# PowerUpDelay-SCR.net
KiCad netlist of a schematic drawn in Altium Designer
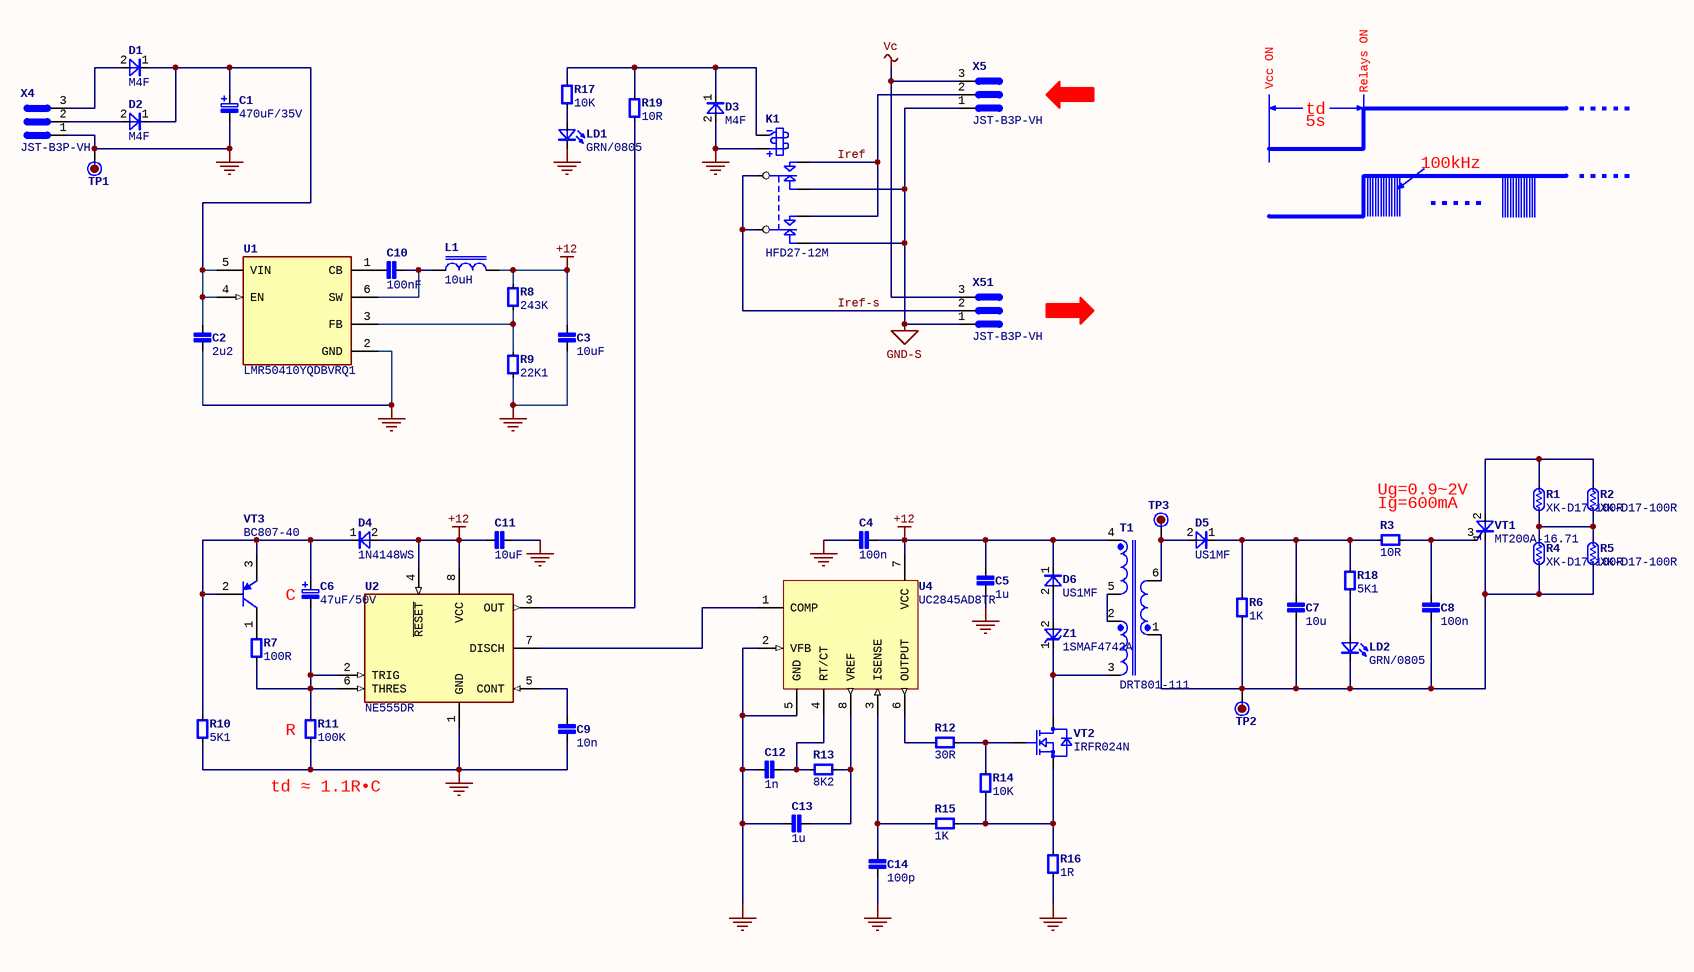
[diagram p0: PowerUpDelay-SCR.SchDoc]

(export (version "E")
  (design (tool "Eeschema 10.0.6"))
  (components
    (comp (ref "C1")
      (value "470uF/35V")
      (footprint "RB5M/D10")
      (libsource (lib "User_leo") (part "CAPACITOR POL(S)"))
    )
    (comp (ref "C2") (value "2u2") (footprint "CAPC1206N") (libsource (lib "*") (part "CAPACITOR(S)")))
    (comp (ref "C3") (value "10uF") (footprint "CAPC0805N") (libsource (lib "*") (part "CAPACITOR(S)")))
    (comp (ref "C4") (value "100n") (footprint "CAPC0805N") (libsource (lib "主控板") (part "CAPACITOR(S)")))
    (comp (ref "C5") (value "1u") (footprint "CAPC0805N") (libsource (lib "主控板") (part "CAPACITOR(S)")))
    (comp (ref "C6")
      (value "47uF/50V")
      (footprint "RB2.5M/D6.3")
      (libsource (lib "User_leo") (part "CAPACITOR POL(S)"))
    )
    (comp (ref "C7") (value "10u") (footprint "CAPC1206N") (libsource (lib "主控板") (part "CAPACITOR(S)")))
    (comp (ref "C8") (value "100n") (footprint "CAPC1206N") (libsource (lib "主控板") (part "CAPACITOR(S)")))
    (comp (ref "C9") (value "10n") (footprint "CAPC0805N") (libsource (lib "主控板") (part "CAPACITOR(S)")))
    (comp (ref "C10") (value "100nF") (footprint "CAPC0805N") (libsource (lib "*") (part "CAPACITOR(S)")))
    (comp (ref "C11") (value "10uF") (footprint "CAPC0805N") (libsource (lib "*") (part "CAPACITOR(S)")))
    (comp (ref "C12") (value "1n") (footprint "CAPC0805N") (libsource (lib "主控板") (part "CAPACITOR(S)")))
    (comp (ref "C13") (value "1u") (footprint "CAPC0805N") (libsource (lib "主控板") (part "CAPACITOR(S)")))
    (comp (ref "C14") (value "100p") (footprint "CAPC0805N") (libsource (lib "主控板") (part "CAPACITOR(S)")))
    (comp (ref "D1")
      (value "M4F")
      (footprint "SMAF")
      (description "二极管")
      (libsource (lib "User_leo") (part "DIODE(S)"))
    )
    (comp (ref "D2")
      (value "M4F")
      (footprint "SMAF")
      (description "二极管")
      (libsource (lib "User_leo") (part "DIODE(S)"))
    )
    (comp (ref "D3")
      (value "M4F")
      (footprint "SMAF")
      (description "二极管")
      (libsource (lib "User_leo") (part "DIODE(S)"))
    )
    (comp (ref "D4")
      (value "1N4148WS")
      (footprint "SOD-323F-1K2A")
      (description "二极管")
      (libsource (lib "User_leo") (part "DIODE(S)"))
    )
    (comp (ref "D5")
      (value "US1MF")
      (footprint "SMAF")
      (description "二极管")
      (libsource (lib "User_leo") (part "DIODE(S)"))
    )
    (comp (ref "D6")
      (value "US1MF")
      (footprint "SMAF")
      (description "二极管")
      (libsource (lib "User_leo") (part "DIODE(S)"))
    )
    (comp (ref "K1")
      (value "HFD27-12M")
      (footprint "RLY-DPDT")
      (description "继电器")
      (libsource (lib "d_user1") (part "RELAY-DPDT"))
    )
    (comp (ref "L1") (value "10uH") (footprint "INDP4040X20N") (libsource (lib "User_leo") (part "IND")))
    (comp (ref "LD1")
      (value "GRN/0805")
      (footprint "LEDC0805N")
      (libsource (lib "ARM-Stub 主控板") (part "LED(S)"))
    )
    (comp (ref "LD2")
      (value "GRN/0805")
      (footprint "LEDC0805N")
      (libsource (lib "ARM-Stub 主控板") (part "LED(S)"))
    )
    (comp (ref "R1")
      (value "XK-D17-100R")
      (footprint "PTC-X17")
      (description "None Liner Resistor")
      (libsource (lib "User_leo") (part "RESISTOR(S) NL"))
    )
    (comp (ref "R2")
      (value "XK-D17-100R")
      (footprint "PTC-X17")
      (description "None Liner Resistor")
      (libsource (lib "User_leo") (part "RESISTOR(S) NL"))
    )
    (comp (ref "R3") (value "10R") (footprint "RESC1206N") (libsource (lib "*") (part "RESISTOR(S)")))
    (comp (ref "R4")
      (value "XK-D17-100R")
      (footprint "PTC-X17")
      (description "None Liner Resistor")
      (libsource (lib "User_leo") (part "RESISTOR(S) NL"))
    )
    (comp (ref "R5")
      (value "XK-D17-100R")
      (footprint "PTC-X17")
      (description "None Liner Resistor")
      (libsource (lib "User_leo") (part "RESISTOR(S) NL"))
    )
    (comp (ref "R6") (value "1K") (footprint "RESC1206N") (libsource (lib "*") (part "RESISTOR(S)")))
    (comp (ref "R7")
      (value "100R")
      (footprint "RESC0805N")
      (description "电阻")
      (libsource (lib "User_leo") (part "RESISTOR(S)"))
    )
    (comp (ref "R8")
      (value "243K")
      (footprint "RESC0805N")
      (description "电阻")
      (libsource (lib "User_leo") (part "RESISTOR(S)"))
    )
    (comp (ref "R9")
      (value "22K1")
      (footprint "RESC0805N")
      (description "电阻")
      (libsource (lib "User_leo") (part "RESISTOR(S)"))
    )
    (comp (ref "R10")
      (value "5K1")
      (footprint "RESC0805N")
      (description "电阻")
      (libsource (lib "User_leo") (part "RESISTOR(S)"))
    )
    (comp (ref "R11") (value "100K") (footprint "RESC0805N") (libsource (lib "*") (part "RESISTOR(S)")))
    (comp (ref "R12") (value "30R") (footprint "RESC0805N") (libsource (lib "*") (part "RESISTOR(S)")))
    (comp (ref "R13") (value "8K2") (footprint "RESC0805N") (libsource (lib "*") (part "RESISTOR(S)")))
    (comp (ref "R14") (value "10K") (footprint "RESC0805N") (libsource (lib "*") (part "RESISTOR(S)")))
    (comp (ref "R15") (value "1K") (footprint "RESC0805N") (libsource (lib "*") (part "RESISTOR(S)")))
    (comp (ref "R16") (value "1R") (footprint "RESC1206N") (libsource (lib "*") (part "RESISTOR(S)")))
    (comp (ref "R17") (value "10K") (footprint "RESC0805N") (libsource (lib "*") (part "RESISTOR(S)")))
    (comp (ref "R18") (value "5K1") (footprint "RESC0805N") (libsource (lib "*") (part "RESISTOR(S)")))
    (comp (ref "R19") (value "10R") (footprint "RESC0805N") (libsource (lib "*") (part "RESISTOR(S)")))
    (comp (ref "T1")
      (value "DRT801-111")
      (footprint "TRANS-DRT801-1+1+1")
      (description "IGBT驱动变压器, DRT801/111, 12.5x16.6mm")
      (libsource (lib "User_leo") (part "TRANSFORM-DRT801-111_FB"))
    )
    (comp (ref "TP1")
      (value "TESTPOINT")
      (footprint "TESTPOINT")
      (description "测试点")
      (libsource (lib "d_user1") (part "TESTPOINT"))
    )
    (comp (ref "TP2")
      (value "TESTPOINT")
      (footprint "TESTPOINT")
      (description "测试点")
      (libsource (lib "d_user1") (part "TESTPOINT"))
    )
    (comp (ref "TP3")
      (value "TESTPOINT")
      (footprint "TESTPOINT")
      (description "测试点")
      (libsource (lib "d_user1") (part "TESTPOINT"))
    )
    (comp (ref "U1")
      (value "LMR50410YQDBVRQ1")
      (footprint "FP-DBV0006A-MFG")
      (description "NIXON PLUS-LMR50410YQDBVRQ1")
      (libsource (lib "Altium Content Vault") (part "dd20875c80c3702360114ef84ecc10b"))
    )
    (comp (ref "U2")
      (value "NE555DR")
      (footprint "FP-D0008A-MFG")
      (description "IC OSC SGL TIMER 100KHZ 8-SOIC")
      (libsource (lib "Altium Content Vault") (part "a29bba90211dec1890110b94dad7d53"))
    )
    (comp (ref "U4")
      (value "UC2845AD8TR")
      (footprint "D0008A_N")
      (fields (field (name "MANUFACTURER") "Texas Instruments"))
      (libsource (lib "Altium Content Vault") (part "TI-UC2845AD8"))
    )
    (comp (ref "VT1")
      (value "MT200A-16.71")
      (footprint "MT200A-16.71")
      (description "晶闸管")
      (libsource (lib "User_leo") (part "SCR(S)"))
    )
    (comp (ref "VT2")
      (value "IRFR024N")
      (footprint "ONSC-DPAK-3-369AA-01_V")
      (description "MOSFET N-CH D-PAK/TO252")
      (fields (field (name "MANUFACTURER") "Fairchild") (field (name "PART NUMBER") "SUD40N08-16-E3"))
      (libsource (lib "User_leo") (part "MOSFET - N-CH"))
    )
    (comp (ref "VT3")
      (value "BC807-40")
      (footprint "SMD USER:SOT-23_N")
      (description "PNP Bipolar Transistor")
      (fields (field (name "PUBLISHER") "Altium Limited"))
      (libsource (lib "User_leo") (part "PNP"))
    )
    (comp (ref "X4")
      (value "JST-B3P-VH")
      (footprint "B3P-VH")
      (description "线路板接插件")
      (libsource (lib "User_leo") (part "3PIN-PCB-Connector"))
    )
    (comp (ref "X5")
      (value "JST-B3P-VH")
      (footprint "B3P-VH")
      (description "线路板接插件")
      (libsource (lib "User_leo") (part "3PIN-PCB-Connector"))
    )
    (comp (ref "X51")
      (value "JST-B3P-VH")
      (footprint "B3P-VH")
      (description "线路板接插件")
      (libsource (lib "User_leo") (part "3PIN-PCB-Connector"))
    )
    (comp (ref "Z1")
      (value "1SMAF4742A")
      (footprint "SMAF")
      (description "齐纳二极管")
      (libsource (lib "User_leo") (part "DIODE ZENER(S)"))
    )
  )
  (nets
    (net (code "1") (name "+12") (class "Default")
      (node (ref "C11") (pin "1") (pinfunction "1_1") (pintype "passive"))
      (node (ref "C3") (pin "1") (pinfunction "1_1") (pintype "passive"))
      (node (ref "C4") (pin "2") (pinfunction "2_2") (pintype "passive"))
      (node (ref "C5") (pin "1") (pinfunction "1_1") (pintype "passive"))
      (node (ref "D4") (pin "2") (pinfunction "A_2") (pintype "passive"))
      (node (ref "D6") (pin "1") (pinfunction "K_1") (pintype "passive"))
      (node (ref "L1") (pin "2") (pinfunction "2_2") (pintype "passive"))
      (node (ref "R8") (pin "2") (pinfunction "2_2") (pintype "passive"))
      (node (ref "T1") (pin "4") (pinfunction "4_4") (pintype "passive"))
      (node (ref "U2") (pin "4") (pinfunction "~{RESET}_4") (pintype "input"))
      (node (ref "U2") (pin "8") (pinfunction "VCC_8") (pintype "power_in"))
      (node (ref "U4") (pin "7") (pinfunction "VCC_7") (pintype "power_in"))
    )
    (net (code "2") (name "/Iref") (class "Default")
      (node (ref "K1") (pin "NO1") (pinfunction "NO1_NO1") (pintype "passive"))
      (node (ref "K1") (pin "NO2") (pinfunction "NO2_NO2") (pintype "passive"))
      (node (ref "X5") (pin "2") (pinfunction "2_2") (pintype "passive"))
    )
    (net (code "3") (name "/Iref-s") (class "Default")
      (node (ref "K1") (pin "COM1") (pinfunction "COMMON1_COM1") (pintype "passive"))
      (node (ref "K1") (pin "COM2") (pinfunction "COMMON2_COM2") (pintype "passive"))
      (node (ref "X51") (pin "2") (pinfunction "2_2") (pintype "passive"))
    )
    (net (code "4") (name "GND") (class "Default")
      (node (ref "C1") (pin "2") (pinfunction "2_2") (pintype "passive"))
      (node (ref "C11") (pin "2") (pinfunction "2_2") (pintype "passive"))
      (node (ref "C12") (pin "1") (pinfunction "1_1") (pintype "passive"))
      (node (ref "C13") (pin "2") (pinfunction "2_2") (pintype "passive"))
      (node (ref "C14") (pin "2") (pinfunction "2_2") (pintype "passive"))
      (node (ref "C2") (pin "2") (pinfunction "2_2") (pintype "passive"))
      (node (ref "C3") (pin "2") (pinfunction "2_2") (pintype "passive"))
      (node (ref "C4") (pin "1") (pinfunction "1_1") (pintype "passive"))
      (node (ref "C5") (pin "2") (pinfunction "2_2") (pintype "passive"))
      (node (ref "C9") (pin "2") (pinfunction "2_2") (pintype "passive"))
      (node (ref "D3") (pin "2") (pinfunction "A_2") (pintype "passive"))
      (node (ref "K1") (pin "COL1") (pinfunction "COIL1_COL1") (pintype "passive"))
      (node (ref "LD1") (pin "2") (pinfunction "K_2") (pintype "passive"))
      (node (ref "R10") (pin "1") (pinfunction "1_1") (pintype "passive"))
      (node (ref "R11") (pin "2") (pinfunction "2_2") (pintype "passive"))
      (node (ref "R16") (pin "2") (pinfunction "2_2") (pintype "passive"))
      (node (ref "R9") (pin "1") (pinfunction "1_1") (pintype "passive"))
      (node (ref "TP1") (pin "1") (pintype "passive"))
      (node (ref "U1") (pin "2") (pinfunction "GND_2") (pintype "power_in"))
      (node (ref "U2") (pin "1") (pinfunction "GND_1") (pintype "power_in"))
      (node (ref "U4") (pin "2") (pinfunction "VFB_2") (pintype "input"))
      (node (ref "U4") (pin "5") (pinfunction "GND_5") (pintype "power_in"))
      (node (ref "X4") (pin "1") (pinfunction "1_1") (pintype "passive"))
    )
    (net (code "5") (name "GND-S") (class "Default")
      (node (ref "K1") (pin "NC1") (pinfunction "NC1_NC1") (pintype "passive"))
      (node (ref "K1") (pin "NC2") (pinfunction "NC2_NC2") (pintype "passive"))
      (node (ref "X5") (pin "1") (pinfunction "1_1") (pintype "passive"))
      (node (ref "X51") (pin "1") (pinfunction "1_1") (pintype "passive"))
    )
    (net (code "6") (name "Net-(D1-A)") (class "Default")
      (node (ref "D1") (pin "2") (pinfunction "A_2") (pintype "passive"))
      (node (ref "X4") (pin "3") (pinfunction "3_3") (pintype "passive"))
    )
    (net (code "7") (name "Net-(D1-K)") (class "Default")
      (node (ref "C1") (pin "1") (pinfunction "1_1") (pintype "passive"))
      (node (ref "C2") (pin "1") (pinfunction "1_1") (pintype "passive"))
      (node (ref "D1") (pin "1") (pinfunction "K_1") (pintype "passive"))
      (node (ref "D2") (pin "1") (pinfunction "K_1") (pintype "passive"))
      (node (ref "U1") (pin "4") (pinfunction "EN_4") (pintype "input"))
      (node (ref "U1") (pin "5") (pinfunction "VIN_5") (pintype "power_in"))
    )
    (net (code "8") (name "Net-(D2-A)") (class "Default")
      (node (ref "D2") (pin "2") (pinfunction "A_2") (pintype "passive"))
      (node (ref "X4") (pin "2") (pinfunction "2_2") (pintype "passive"))
    )
    (net (code "9") (name "Net-(D3-K)") (class "Default")
      (node (ref "D3") (pin "1") (pinfunction "K_1") (pintype "passive"))
      (node (ref "K1") (pin "COL2") (pinfunction "COIL2_COL2") (pintype "passive"))
      (node (ref "R17") (pin "1") (pinfunction "1_1") (pintype "passive"))
      (node (ref "R19") (pin "1") (pinfunction "1_1") (pintype "passive"))
    )
    (net (code "10") (name "Net-(D4-K)") (class "Default")
      (node (ref "C6") (pin "1") (pinfunction "1_1") (pintype "passive"))
      (node (ref "D4") (pin "1") (pinfunction "K_1") (pintype "passive"))
      (node (ref "R10") (pin "2") (pinfunction "2_2") (pintype "passive"))
      (node (ref "VT3") (pin "2") (pinfunction "B_2") (pintype "passive"))
      (node (ref "VT3") (pin "3") (pinfunction "E_3") (pintype "passive"))
    )
    (net (code "11") (name "Net-(D5-A)") (class "Default")
      (node (ref "D5") (pin "2") (pinfunction "A_2") (pintype "passive"))
      (node (ref "T1") (pin "6") (pinfunction "6_6") (pintype "passive"))
      (node (ref "TP3") (pin "1") (pintype "passive"))
    )
    (net (code "12") (name "Net-(D5-K)") (class "Default")
      (node (ref "C7") (pin "1") (pinfunction "1_1") (pintype "passive"))
      (node (ref "D5") (pin "1") (pinfunction "K_1") (pintype "passive"))
      (node (ref "R18") (pin "1") (pinfunction "1_1") (pintype "passive"))
      (node (ref "R3") (pin "1") (pinfunction "1_1") (pintype "passive"))
      (node (ref "R6") (pin "1") (pinfunction "1_1") (pintype "passive"))
    )
    (net (code "13") (name "Net-(D6-A)") (class "Default")
      (node (ref "D6") (pin "2") (pinfunction "A_2") (pintype "passive"))
      (node (ref "Z1") (pin "2") (pinfunction "A_2") (pintype "passive"))
    )
    (net (code "14") (name "Net-(LD1-A)") (class "Default")
      (node (ref "LD1") (pin "1") (pinfunction "A_1") (pintype "passive"))
      (node (ref "R17") (pin "2") (pinfunction "2_2") (pintype "passive"))
    )
    (net (code "15") (name "Net-(LD2-A)") (class "Default")
      (node (ref "LD2") (pin "1") (pinfunction "A_1") (pintype "passive"))
      (node (ref "R18") (pin "2") (pinfunction "2_2") (pintype "passive"))
    )
    (net (code "16") (name "Net-(LD2-K)") (class "Default")
      (node (ref "C7") (pin "2") (pinfunction "2_2") (pintype "passive"))
      (node (ref "C8") (pin "2") (pinfunction "2_2") (pintype "passive"))
      (node (ref "LD2") (pin "2") (pinfunction "K_2") (pintype "passive"))
      (node (ref "R4") (pin "1") (pinfunction "1_1") (pintype "passive"))
      (node (ref "R5") (pin "1") (pinfunction "1_1") (pintype "passive"))
      (node (ref "R6") (pin "2") (pinfunction "2_2") (pintype "passive"))
      (node (ref "T1") (pin "1") (pinfunction "1_1") (pintype "passive"))
      (node (ref "TP2") (pin "1") (pintype "passive"))
      (node (ref "VT1") (pin "1") (pinfunction "K_1") (pintype "passive"))
    )
    (net (code "17") (name "Net-(R1-Pad1)") (class "Default")
      (node (ref "R1") (pin "1") (pinfunction "1_1") (pintype "passive"))
      (node (ref "R2") (pin "1") (pinfunction "1_1") (pintype "passive"))
      (node (ref "R4") (pin "2") (pinfunction "2_2") (pintype "passive"))
      (node (ref "R5") (pin "2") (pinfunction "2_2") (pintype "passive"))
    )
    (net (code "18") (name "Net-(T1-Pad2)") (class "Default")
      (node (ref "T1") (pin "2") (pinfunction "2_2") (pintype "passive"))
      (node (ref "T1") (pin "5") (pinfunction "5_5") (pintype "passive"))
    )
    (net (code "19") (name "Net-(U1-CB)") (class "Default")
      (node (ref "C10") (pin "1") (pinfunction "1_1") (pintype "passive"))
      (node (ref "U1") (pin "1") (pinfunction "CB_1") (pintype "passive"))
    )
    (net (code "20") (name "Net-(U1-FB)") (class "Default")
      (node (ref "R8") (pin "1") (pinfunction "1_1") (pintype "passive"))
      (node (ref "R9") (pin "2") (pinfunction "2_2") (pintype "passive"))
      (node (ref "U1") (pin "3") (pinfunction "FB_3") (pintype "passive"))
    )
    (net (code "21") (name "Net-(U1-SW)") (class "Default")
      (node (ref "C10") (pin "2") (pinfunction "2_2") (pintype "passive"))
      (node (ref "L1") (pin "1") (pinfunction "1_1") (pintype "passive"))
      (node (ref "U1") (pin "6") (pinfunction "SW_6") (pintype "power_in"))
    )
    (net (code "22") (name "Net-(U2-CONT)") (class "Default")
      (node (ref "C9") (pin "1") (pinfunction "1_1") (pintype "passive"))
      (node (ref "U2") (pin "5") (pinfunction "CONT_5") (pintype "input"))
    )
    (net (code "23") (name "Net-(U2-DISCH)") (class "Default")
      (node (ref "U2") (pin "7") (pinfunction "DISCH_7") (pintype "open_collector"))
      (node (ref "U4") (pin "1") (pinfunction "COMP_1") (pintype "passive"))
    )
    (net (code "24") (name "Net-(U2-OUT)") (class "Default")
      (node (ref "R19") (pin "2") (pinfunction "2_2") (pintype "passive"))
      (node (ref "U2") (pin "3") (pinfunction "OUT_3") (pintype "output"))
    )
    (net (code "25") (name "Net-(U2-THRES)") (class "Default")
      (node (ref "C6") (pin "2") (pinfunction "2_2") (pintype "passive"))
      (node (ref "R11") (pin "1") (pinfunction "1_1") (pintype "passive"))
      (node (ref "R7") (pin "2") (pinfunction "2_2") (pintype "passive"))
      (node (ref "U2") (pin "2") (pinfunction "TRIG_2") (pintype "input"))
      (node (ref "U2") (pin "6") (pinfunction "THRES_6") (pintype "input"))
    )
    (net (code "26") (name "Net-(U4-ISENSE)") (class "Default")
      (node (ref "C14") (pin "1") (pinfunction "1_1") (pintype "passive"))
      (node (ref "R15") (pin "1") (pinfunction "1_1") (pintype "passive"))
      (node (ref "U4") (pin "3") (pinfunction "ISENSE_3") (pintype "input"))
    )
    (net (code "27") (name "Net-(U4-OUTPUT)") (class "Default")
      (node (ref "R12") (pin "2") (pinfunction "2_2") (pintype "passive"))
      (node (ref "U4") (pin "6") (pinfunction "OUTPUT_6") (pintype "output"))
    )
    (net (code "28") (name "Net-(U4-RT{slash}CT)") (class "Default")
      (node (ref "C12") (pin "2") (pinfunction "2_2") (pintype "passive"))
      (node (ref "R13") (pin "2") (pinfunction "2_2") (pintype "passive"))
      (node (ref "U4") (pin "4") (pinfunction "RT/CT_4") (pintype "passive"))
    )
    (net (code "29") (name "Net-(U4-VREF)") (class "Default")
      (node (ref "C13") (pin "1") (pinfunction "1_1") (pintype "passive"))
      (node (ref "R13") (pin "1") (pinfunction "1_1") (pintype "passive"))
      (node (ref "U4") (pin "8") (pinfunction "VREF_8") (pintype "output"))
    )
    (net (code "30") (name "Net-(VT1-A)") (class "Default")
      (node (ref "R1") (pin "2") (pinfunction "2_2") (pintype "passive"))
      (node (ref "R2") (pin "2") (pinfunction "2_2") (pintype "passive"))
      (node (ref "VT1") (pin "2") (pinfunction "A_2") (pintype "passive"))
    )
    (net (code "31") (name "Net-(VT1-G)") (class "Default")
      (node (ref "C8") (pin "1") (pinfunction "1_1") (pintype "passive"))
      (node (ref "R3") (pin "2") (pinfunction "2_2") (pintype "passive"))
      (node (ref "VT1") (pin "3") (pinfunction "G_3") (pintype "passive"))
    )
    (net (code "32") (name "Net-(VT2-D)") (class "Default")
      (node (ref "T1") (pin "3") (pinfunction "3_3") (pintype "passive"))
      (node (ref "VT2") (pin "4") (pinfunction "D_4") (pintype "passive"))
      (node (ref "Z1") (pin "1") (pinfunction "K_1") (pintype "passive"))
    )
    (net (code "33") (name "Net-(VT2-G)") (class "Default")
      (node (ref "R12") (pin "1") (pinfunction "1_1") (pintype "passive"))
      (node (ref "R14") (pin "1") (pinfunction "1_1") (pintype "passive"))
      (node (ref "VT2") (pin "1") (pinfunction "G_1") (pintype "passive"))
    )
    (net (code "34") (name "Net-(VT2-S)") (class "Default")
      (node (ref "R14") (pin "2") (pinfunction "2_2") (pintype "passive"))
      (node (ref "R15") (pin "2") (pinfunction "2_2") (pintype "passive"))
      (node (ref "R16") (pin "1") (pinfunction "1_1") (pintype "passive"))
      (node (ref "VT2") (pin "3") (pinfunction "S_3") (pintype "passive"))
    )
    (net (code "35") (name "Net-(VT3-C)") (class "Default")
      (node (ref "R7") (pin "1") (pinfunction "1_1") (pintype "passive"))
      (node (ref "VT3") (pin "1") (pinfunction "C_1") (pintype "passive"))
    )
    (net (code "36") (name "Vc") (class "Default")
      (node (ref "X5") (pin "3") (pinfunction "3_3") (pintype "passive"))
      (node (ref "X51") (pin "3") (pinfunction "3_3") (pintype "passive"))
    )
  )
)
